# Protection.net
KiCad netlist of a schematic drawn in Altium Designer
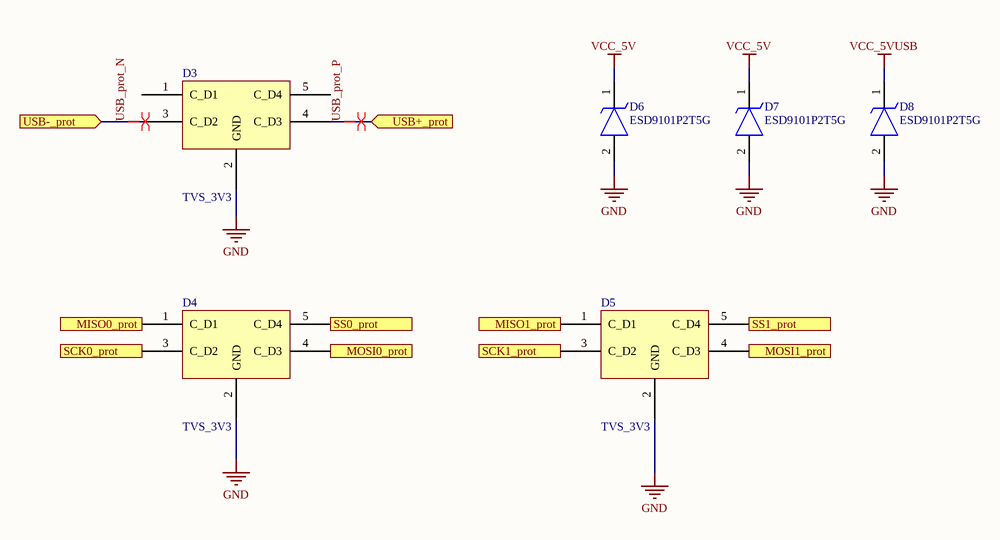
[diagram p0: Protection.SchDoc]

(export (version "E")
  (design (tool "Eeschema 10.0.6"))
  (components
    (comp (ref "D3")
      (value "TVS_3V3")
      (footprint "SOT353")
      (description "4 TVS dedicated for 3.3V circuits")
      (fields (field (name "MANUFACTURER") "Nexperia"))
      (libsource (lib "passiveComponents") (part "TVS_3V3"))
    )
    (comp (ref "D4")
      (value "TVS_3V3")
      (footprint "SOT353")
      (description "4 TVS dedicated for 3.3V circuits")
      (fields (field (name "MANUFACTURER") "Nexperia"))
      (libsource (lib "passiveComponents") (part "TVS_3V3"))
    )
    (comp (ref "D5")
      (value "TVS_3V3")
      (footprint "SOT353")
      (description "4 TVS dedicated for 3.3V circuits")
      (fields (field (name "MANUFACTURER") "Nexperia"))
      (libsource (lib "passiveComponents") (part "TVS_3V3"))
    )
    (comp (ref "D6")
      (value "ESD9101P2T5G")
      (footprint "MouserDropbox:SODFL1006X40N")
      (description "TVS Diode (Uni-directional)")
      (fields (field (name "MOUSER PART NUMBER") "863-ESD9101P2T5G"))
      (libsource (lib "*") (part "ESD9101P2T5G"))
    )
    (comp (ref "D7")
      (value "ESD9101P2T5G")
      (footprint "MouserDropbox:SODFL1006X40N")
      (description "TVS Diode (Uni-directional)")
      (fields (field (name "MOUSER PART NUMBER") "863-ESD9101P2T5G"))
      (libsource (lib "*") (part "ESD9101P2T5G"))
    )
    (comp (ref "D8")
      (value "ESD9101P2T5G")
      (footprint "MouserDropbox:SODFL1006X40N")
      (description "TVS Diode (Uni-directional)")
      (fields (field (name "MOUSER PART NUMBER") "863-ESD9101P2T5G"))
      (libsource (lib "*") (part "ESD9101P2T5G"))
    )
  )
  (nets
    (net (code "1") (name "/MISO0_prot") (class "Default")
      (node (ref "D4") (pin "1") (pinfunction "C_D1_1") (pintype "passive"))
    )
    (net (code "2") (name "/MISO1_prot") (class "Default")
      (node (ref "D5") (pin "1") (pinfunction "C_D1_1") (pintype "passive"))
    )
    (net (code "3") (name "/MOSI0_prot") (class "Default")
      (node (ref "D4") (pin "4") (pinfunction "C_D3_4") (pintype "passive"))
    )
    (net (code "4") (name "/MOSI1_prot") (class "Default")
      (node (ref "D5") (pin "4") (pinfunction "C_D3_4") (pintype "passive"))
    )
    (net (code "5") (name "/SCK0_prot") (class "Default")
      (node (ref "D4") (pin "3") (pinfunction "C_D2_3") (pintype "passive"))
    )
    (net (code "6") (name "/SCK1_prot") (class "Default")
      (node (ref "D5") (pin "3") (pinfunction "C_D2_3") (pintype "passive"))
    )
    (net (code "7") (name "/SS0_prot") (class "Default")
      (node (ref "D4") (pin "5") (pinfunction "C_D4_5") (pintype "passive"))
    )
    (net (code "8") (name "/SS1_prot") (class "Default")
      (node (ref "D5") (pin "5") (pinfunction "C_D4_5") (pintype "passive"))
    )
    (net (code "9") (name "/USB_prot_N") (class "Default")
      (node (ref "D3") (pin "3") (pinfunction "C_D2_3") (pintype "passive"))
    )
    (net (code "10") (name "/USB_prot_P") (class "Default")
      (node (ref "D3") (pin "4") (pinfunction "C_D3_4") (pintype "passive"))
    )
    (net (code "11") (name "GND") (class "Default")
      (node (ref "D3") (pin "2") (pinfunction "GND_2") (pintype "passive"))
      (node (ref "D4") (pin "2") (pinfunction "GND_2") (pintype "passive"))
      (node (ref "D5") (pin "2") (pinfunction "GND_2") (pintype "passive"))
      (node (ref "D6") (pin "2") (pinfunction "A_2") (pintype "passive"))
      (node (ref "D7") (pin "2") (pinfunction "A_2") (pintype "passive"))
      (node (ref "D8") (pin "2") (pinfunction "A_2") (pintype "passive"))
    )
    (net (code "12") (name "VCC_5V") (class "Default")
      (node (ref "D6") (pin "1") (pinfunction "K_1") (pintype "passive"))
      (node (ref "D7") (pin "1") (pinfunction "K_1") (pintype "passive"))
    )
    (net (code "13") (name "VCC_5VUSB") (class "Default")
      (node (ref "D8") (pin "1") (pinfunction "K_1") (pintype "passive"))
    )
    (net (code "14") (name "unconnected-(D3-C_D1-Pad1)") (class "Default")
      (node (ref "D3") (pin "1") (pinfunction "C_D1_1") (pintype "passive"))
    )
    (net (code "15") (name "unconnected-(D3-C_D4-Pad5)") (class "Default")
      (node (ref "D3") (pin "5") (pinfunction "C_D4_5") (pintype "passive"))
    )
  )
)
